# DWM_Display.net
KiCad netlist of a schematic drawn in Altium Designer
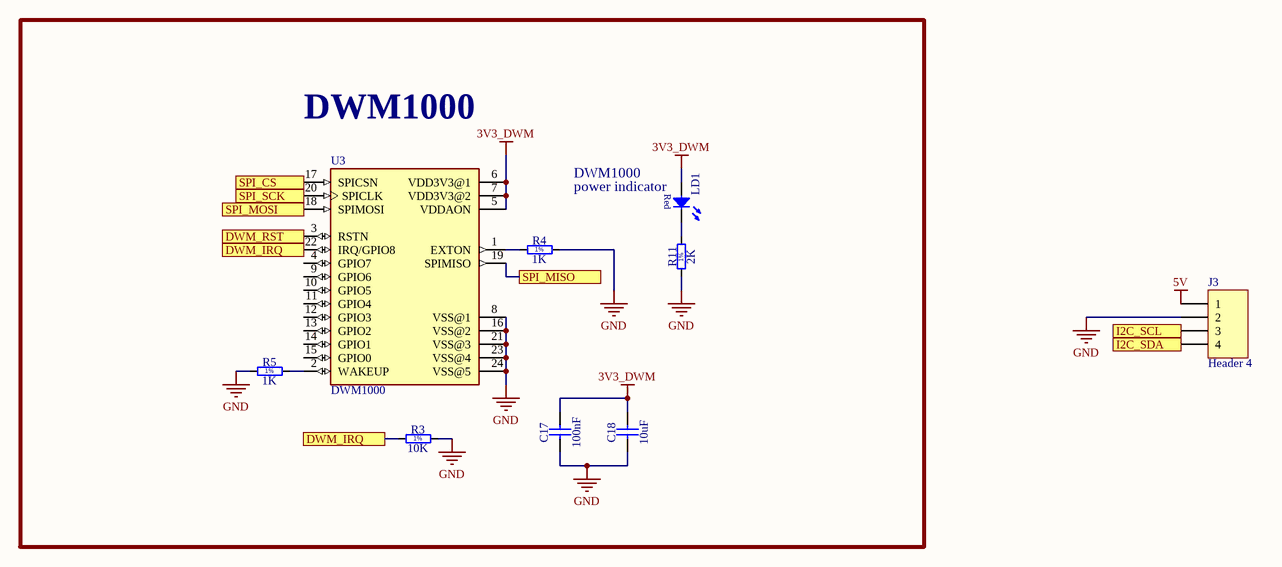
[diagram p0: DWM_Display.SchDoc]

(export (version "E")
  (design (tool "Eeschema 10.0.6"))
  (components
    (comp (ref "C17")
      (value "100nF")
      (footprint "0603C")
      (description "Non-polarised capacitor")
      (libsource (lib "Universal Acq") (part "Capacitor - non polarized"))
    )
    (comp (ref "C18")
      (value "10uF")
      (footprint "0603C")
      (description "Non-polarised capacitor")
      (libsource (lib "Universal Acq") (part "Capacitor - non polarized"))
    )
    (comp (ref "J3")
      (value "Header 4")
      (footprint "HDR1X4")
      (description "Header, 4-Pin")
      (fields (field (name "PUBLISHER") "Altium Limited"))
      (libsource (lib "Miscellaneous Connectors") (part "Header 4"))
    )
    (comp (ref "LD1")
      (value "~")
      (footprint "0603 LED")
      (description "LED Red 1C 2A")
      (libsource (lib "Universal Acq") (part "LED Red 1C 2A"))
    )
    (comp (ref "R3")
      (value "10K")
      (footprint "0603R")
      (description "Resistor - 1%")
      (libsource (lib "Universal Acq") (part "Resistor - 1%_1"))
    )
    (comp (ref "R4")
      (value "1K")
      (footprint "0603R")
      (description "Resistor - 1%")
      (libsource (lib "Universal Acq") (part "Resistor - 1%_1"))
    )
    (comp (ref "R5")
      (value "1K")
      (footprint "0603R")
      (description "Resistor - 1%")
      (libsource (lib "Universal Acq") (part "Resistor - 1%_1"))
    )
    (comp (ref "R11")
      (value "2K")
      (footprint "0603R")
      (description "Resistor - 1%")
      (libsource (lib "Universal Acq") (part "Resistor - 1%_1"))
    )
    (comp (ref "U3")
      (value "DWM1000")
      (footprint "XCVR_DWM1000")
      (description "802.15.4 IR-UWB Transceiver Module 3.5GHz ~ 6.5GHz Integrated, Chip Surface Mount")
      (fields (field (name "MF") "Decawave Limited"))
      (libsource (lib "DWM1000") (part "DWM1000"))
    )
  )
  (nets
    (net (code "1") (name "/DWM_IRQ") (class "Default")
      (node (ref "R3") (pin "1") (pinfunction "1_1") (pintype "passive"))
      (node (ref "U3") (pin "22") (pinfunction "IRQ/GPIO8_22") (pintype "bidirectional"))
    )
    (net (code "2") (name "/DWM_RST") (class "Default")
      (node (ref "U3") (pin "3") (pinfunction "RSTN_3") (pintype "bidirectional"))
    )
    (net (code "3") (name "/I2C_SCL") (class "Default")
      (node (ref "J3") (pin "3") (pinfunction "3_3") (pintype "passive"))
    )
    (net (code "4") (name "/I2C_SDA") (class "Default")
      (node (ref "J3") (pin "4") (pinfunction "4_4") (pintype "passive"))
    )
    (net (code "5") (name "/SPI_CS") (class "Default")
      (node (ref "U3") (pin "17") (pinfunction "SPICSN_17") (pintype "input"))
    )
    (net (code "6") (name "/SPI_MISO") (class "Default")
      (node (ref "U3") (pin "19") (pinfunction "SPIMISO_19") (pintype "output"))
    )
    (net (code "7") (name "/SPI_MOSI") (class "Default")
      (node (ref "U3") (pin "18") (pinfunction "SPIMOSI_18") (pintype "input"))
    )
    (net (code "8") (name "/SPI_SCK") (class "Default")
      (node (ref "U3") (pin "20") (pinfunction "SPICLK_20") (pintype "input"))
    )
    (net (code "9") (name "3V3_DWM") (class "Default")
      (node (ref "C17") (pin "2") (pinfunction "2_2") (pintype "passive"))
      (node (ref "C18") (pin "2") (pinfunction "2_2") (pintype "passive"))
      (node (ref "LD1") (pin "2") (pinfunction "A_2") (pintype "passive"))
      (node (ref "U3") (pin "5") (pinfunction "VDDAON_5") (pintype "power_in"))
      (node (ref "U3") (pin "6") (pinfunction "VDD3V3@1_6") (pintype "power_in"))
      (node (ref "U3") (pin "7") (pinfunction "VDD3V3@2_7") (pintype "power_in"))
    )
    (net (code "10") (name "5V") (class "Default")
      (node (ref "J3") (pin "1") (pinfunction "1_1") (pintype "passive"))
    )
    (net (code "11") (name "GND") (class "Default")
      (node (ref "C17") (pin "1") (pinfunction "1_1") (pintype "passive"))
      (node (ref "C18") (pin "1") (pinfunction "1_1") (pintype "passive"))
      (node (ref "J3") (pin "2") (pinfunction "2_2") (pintype "passive"))
      (node (ref "R11") (pin "1") (pinfunction "1_1") (pintype "passive"))
      (node (ref "R3") (pin "2") (pinfunction "2_2") (pintype "passive"))
      (node (ref "R4") (pin "2") (pinfunction "2_2") (pintype "passive"))
      (node (ref "R5") (pin "1") (pinfunction "1_1") (pintype "passive"))
      (node (ref "U3") (pin "16") (pinfunction "VSS@2_16") (pintype "power_in"))
      (node (ref "U3") (pin "21") (pinfunction "VSS@3_21") (pintype "power_in"))
      (node (ref "U3") (pin "23") (pinfunction "VSS@4_23") (pintype "power_in"))
      (node (ref "U3") (pin "24") (pinfunction "VSS@5_24") (pintype "power_in"))
      (node (ref "U3") (pin "8") (pinfunction "VSS@1_8") (pintype "power_in"))
    )
    (net (code "12") (name "Net-(LD1-C)") (class "Default")
      (node (ref "LD1") (pin "1") (pinfunction "C_1") (pintype "passive"))
      (node (ref "R11") (pin "2") (pinfunction "2_2") (pintype "passive"))
    )
    (net (code "13") (name "Net-(U3-EXTON)") (class "Default")
      (node (ref "R4") (pin "1") (pinfunction "1_1") (pintype "passive"))
      (node (ref "U3") (pin "1") (pinfunction "EXTON_1") (pintype "output"))
    )
    (net (code "14") (name "Net-(U3-WAKEUP)") (class "Default")
      (node (ref "R5") (pin "2") (pinfunction "2_2") (pintype "passive"))
      (node (ref "U3") (pin "2") (pinfunction "WAKEUP_2") (pintype "bidirectional"))
    )
    (net (code "15") (name "unconnected-(U3-GPIO0-Pad15)") (class "Default")
      (node (ref "U3") (pin "15") (pinfunction "GPIO0_15") (pintype "bidirectional"))
    )
    (net (code "16") (name "unconnected-(U3-GPIO1-Pad14)") (class "Default")
      (node (ref "U3") (pin "14") (pinfunction "GPIO1_14") (pintype "bidirectional"))
    )
    (net (code "17") (name "unconnected-(U3-GPIO2-Pad13)") (class "Default")
      (node (ref "U3") (pin "13") (pinfunction "GPIO2_13") (pintype "bidirectional"))
    )
    (net (code "18") (name "unconnected-(U3-GPIO3-Pad12)") (class "Default")
      (node (ref "U3") (pin "12") (pinfunction "GPIO3_12") (pintype "bidirectional"))
    )
    (net (code "19") (name "unconnected-(U3-GPIO4-Pad11)") (class "Default")
      (node (ref "U3") (pin "11") (pinfunction "GPIO4_11") (pintype "bidirectional"))
    )
    (net (code "20") (name "unconnected-(U3-GPIO5-Pad10)") (class "Default")
      (node (ref "U3") (pin "10") (pinfunction "GPIO5_10") (pintype "bidirectional"))
    )
    (net (code "21") (name "unconnected-(U3-GPIO6-Pad9)") (class "Default")
      (node (ref "U3") (pin "9") (pinfunction "GPIO6_9") (pintype "bidirectional"))
    )
    (net (code "22") (name "unconnected-(U3-GPIO7-Pad4)") (class "Default")
      (node (ref "U3") (pin "4") (pinfunction "GPIO7_4") (pintype "bidirectional"))
    )
  )
)
